# Blue_Clipper.net
KiCad netlist of a schematic drawn in Altium Designer
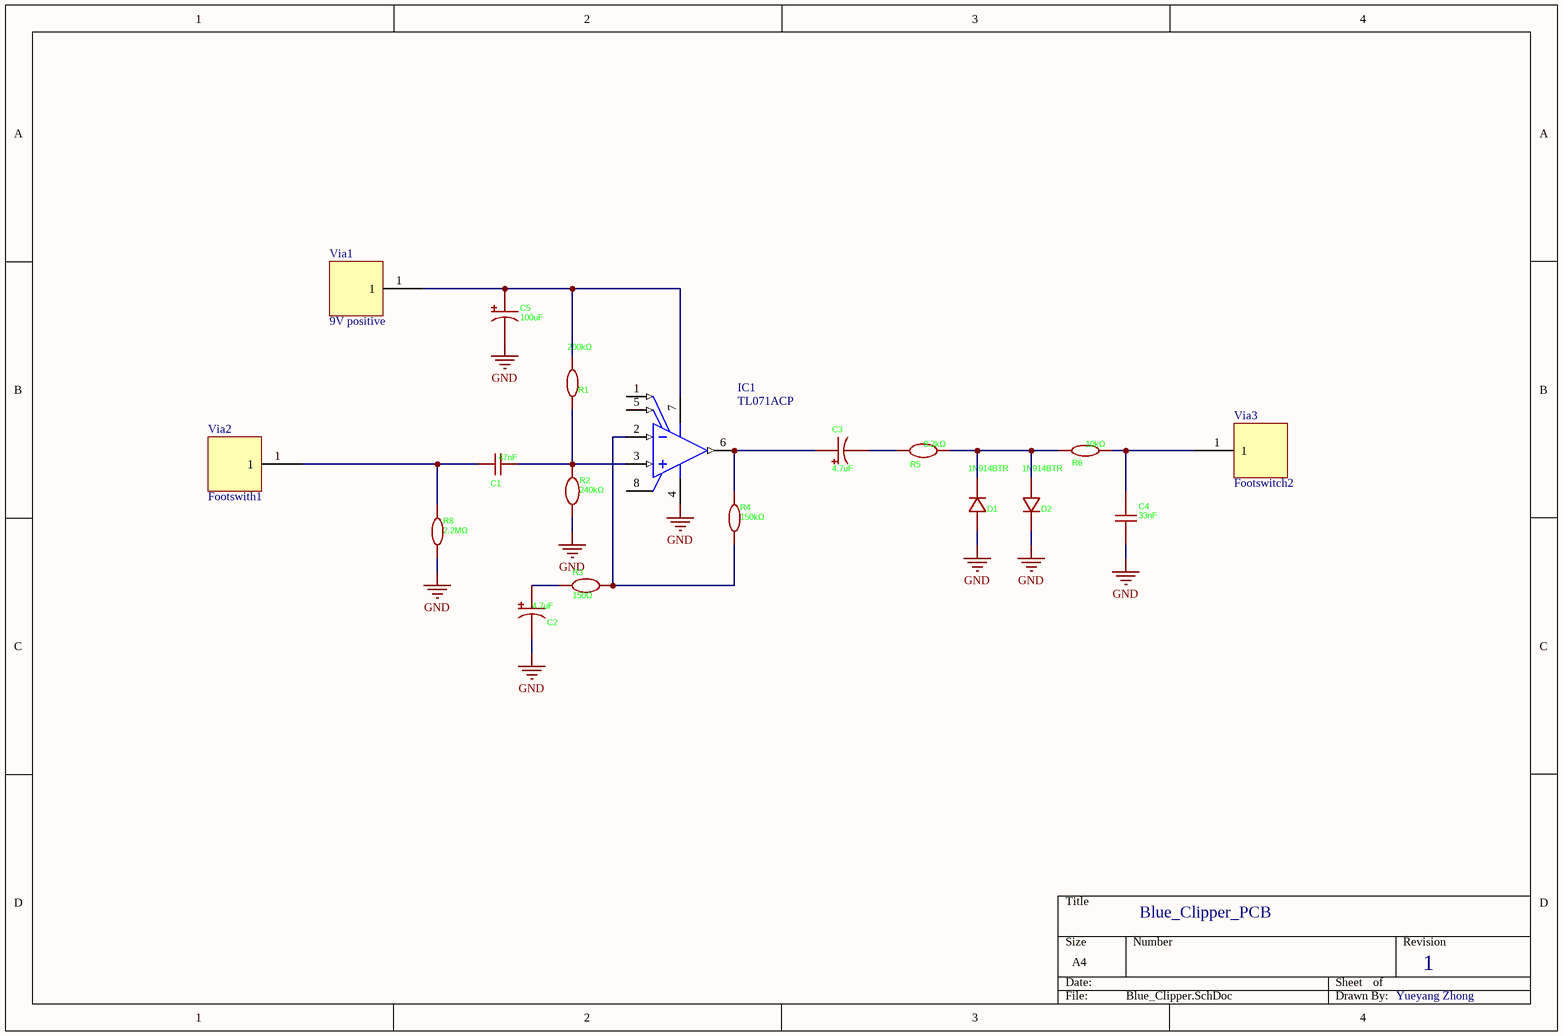
[diagram p0: Blue_Clipper.SchDoc]

(export (version "E")
  (design (tool "Eeschema 10.0.6"))
  (components
    (comp (ref "C1")
      (value "47nF")
      (footprint "47nF")
      (fields
        (field (name "MANUFACTURER") "SRD(圣融达)")
        (field (name "MANUFACTURER PART") "MPP473K2E1304095LC")
        (field (name "TOLERANCE") "±10%")
      )
      (libsource (lib "Schlib1") (part "MPP473K2E1304095LC"))
    )
    (comp (ref "C2")
      (value "4.7uF")
      (footprint "4.7uF")
      (fields
        (field (name "MANUFACTURER") "Nichicon(尼吉康)")
        (field (name "MANUFACTURER PART") "UUD1V4R7MCL1GS")
        (field (name "TOLERANCE") "±20%")
      )
      (libsource (lib "Schlib1") (part "UUD1V4R7MCL1GS"))
    )
    (comp (ref "C3")
      (value "4.7uF")
      (footprint "4.7uF")
      (fields
        (field (name "MANUFACTURER") "Nichicon(尼吉康)")
        (field (name "MANUFACTURER PART") "UUD1V4R7MCL1GS")
        (field (name "TOLERANCE") "±20%")
      )
      (libsource (lib "Schlib1") (part "UUD1V4R7MCL1GS"))
    )
    (comp (ref "C4")
      (value "33nF")
      (footprint "33nF")
      (fields
        (field (name "MANUFACTURER") "KYET(科雅)")
        (field (name "MANUFACTURER PART") "KP333J2J1001")
        (field (name "TOLERANCE") "±5%")
      )
      (libsource (lib "Schlib1") (part "KP333J2J1001"))
    )
    (comp (ref "C5")
      (value "100uF")
      (footprint "100nF")
      (fields
        (field (name "MANUFACTURER") "rubycon(红宝石)")
        (field (name "MANUFACTURER PART") "50TZV100M8X10.5")
        (field (name "TOLERANCE") "±20%")
      )
      (libsource (lib "Schlib1") (part "50TZV100M8X10.5"))
    )
    (comp (ref "D1")
      (value "1N914BTR")
      (footprint "DO-35_BD2.0-L4.2-P8.20-D0.5-RD")
      (fields (field (name "MANUFACTURER") "onsemi(安森美)"))
      (libsource (lib "diodes") (part "1N914BTR"))
    )
    (comp (ref "D2")
      (value "1N914BTR")
      (footprint "DO-35_BD2.0-L4.2-P8.20-D0.5-RD")
      (fields (field (name "MANUFACTURER") "onsemi(安森美)"))
      (libsource (lib "diodes") (part "1N914BTR"))
    )
    (comp (ref "IC1")
      (value "TL071ACP")
      (footprint "P0008A")
      (fields (field (name "MANUFACTURER") "Texas Instruments"))
      (libsource (lib "Altium Content Vault") (part "TI-AMP-S5-2-8"))
    )
    (comp (ref "R1")
      (value "200kΩ")
      (footprint "200K")
      (description "200K")
      (fields (field (name "MANUFACTURER") "VO(翔胜)") (field (name "MANUFACTURER PART") "CR1W-200K±5%-TT52"))
      (libsource (lib "Schlib1") (part "CR1W-200K±5%-TT52"))
    )
    (comp (ref "R2")
      (value "240kΩ")
      (footprint "240K")
      (description "240K")
      (fields (field (name "MANUFACTURER") "VO(翔胜)") (field (name "MANUFACTURER PART") "MO2W-240K±5%-9T73"))
      (libsource (lib "Schlib1") (part "MO2W-240K±5%-9T73"))
    )
    (comp (ref "R3")
      (value "150Ω")
      (footprint "150")
      (description "150")
      (fields (field (name "MANUFACTURER") "VO(翔胜)") (field (name "MANUFACTURER PART") "CR1/2W-150Ω±5%-XT52"))
      (libsource (lib "Schlib1") (part "CR1/2W-150Ω±5%-XT52"))
    )
    (comp (ref "R4")
      (value "150kΩ")
      (footprint "150K")
      (description "150K")
      (fields
        (field (name "MANUFACTURER") "UNI-ROYAL(厚声)")
        (field (name "MANUFACTURER PART") "MFR03SF1503A10")
      )
      (libsource (lib "Schlib1") (part "MFR03SF1503A10"))
    )
    (comp (ref "R5")
      (value "8.2kΩ")
      (footprint "8K2")
      (description "8.2K")
      (fields (field (name "MANUFACTURER") "VO(翔胜)") (field (name "MANUFACTURER PART") "CR1/2W-8K2±5%-2T52"))
      (libsource (lib "Schlib1") (part "CR1/2W-8K2±5%-2T52"))
    )
    (comp (ref "R6")
      (value "10kΩ")
      (footprint "10K")
      (description "10K")
      (fields (field (name "MANUFACTURER") "VO(翔胜)") (field (name "MANUFACTURER PART") "CR1/2W-10K±5%-2T52"))
      (libsource (lib "Schlib1") (part "CR1/2W-10K±5%-2T52"))
    )
    (comp (ref "R8")
      (value "2.2MΩ")
      (footprint "2.2M")
      (description "2.2M")
      (fields
        (field (name "MANUFACTURER") "CCO(千志电子)")
        (field (name "MANUFACTURER PART") "CF1/2W-2.2MΩ±5% T")
      )
      (libsource (lib "Schlib1") (part "CF1/2W-2.2MΩ±5% T"))
    )
    (comp (ref "Via1")
      (value "9V positive")
      (footprint "PCBComponent_1")
      (libsource (lib "Schlib1") (part "Via"))
    )
    (comp (ref "Via2")
      (value "Footswith1")
      (footprint "PCBComponent_1")
      (libsource (lib "Schlib1") (part "Via"))
    )
    (comp (ref "Via3") (value "Footswitch2") (footprint "PCBComponent_1") (libsource (lib "") (part "Via_1")))
  )
  (nets
    (net (code "1") (name "GND") (class "Default")
      (node (ref "C2") (pin "2") (pinfunction "2_2") (pintype "passive"))
      (node (ref "C4") (pin "1") (pinfunction "1_1") (pintype "passive"))
      (node (ref "C5") (pin "2") (pinfunction "2_2") (pintype "passive"))
      (node (ref "D1") (pin "2") (pinfunction "2_2") (pintype "passive"))
      (node (ref "D2") (pin "1") (pinfunction "1_1") (pintype "passive"))
      (node (ref "IC1") (pin "4") (pinfunction "VCC-_4") (pintype "power_in"))
      (node (ref "R2") (pin "1") (pinfunction "1_1") (pintype "passive"))
      (node (ref "R8") (pin "1") (pinfunction "1_1") (pintype "passive"))
    )
    (net (code "2") (name "Net-(C1-Pad1)") (class "Default")
      (node (ref "C1") (pin "1") (pinfunction "1_1") (pintype "passive"))
      (node (ref "R8") (pin "2") (pinfunction "2_2") (pintype "passive"))
      (node (ref "Via2") (pin "1") (pinfunction "1_1") (pintype "passive"))
    )
    (net (code "3") (name "Net-(C2-Pad1)") (class "Default")
      (node (ref "C2") (pin "1") (pinfunction "1_1") (pintype "passive"))
      (node (ref "R3") (pin "2") (pinfunction "2_2") (pintype "passive"))
    )
    (net (code "4") (name "Net-(C3-Pad2)") (class "Default")
      (node (ref "C3") (pin "2") (pinfunction "2_2") (pintype "passive"))
      (node (ref "R5") (pin "1") (pinfunction "1_1") (pintype "passive"))
    )
    (net (code "5") (name "Net-(C4-Pad2)") (class "Default")
      (node (ref "C4") (pin "2") (pinfunction "2_2") (pintype "passive"))
      (node (ref "R6") (pin "2") (pinfunction "2_2") (pintype "passive"))
      (node (ref "Via3") (pin "1") (pinfunction "1_1") (pintype "passive"))
    )
    (net (code "6") (name "Net-(D1-Pad1)") (class "Default")
      (node (ref "D1") (pin "1") (pinfunction "1_1") (pintype "passive"))
      (node (ref "D2") (pin "2") (pinfunction "2_2") (pintype "passive"))
      (node (ref "R5") (pin "2") (pinfunction "2_2") (pintype "passive"))
      (node (ref "R6") (pin "1") (pinfunction "1_1") (pintype "passive"))
    )
    (net (code "7") (name "Net-(IC1-IN+)") (class "Default")
      (node (ref "C1") (pin "2") (pinfunction "2_2") (pintype "passive"))
      (node (ref "IC1") (pin "3") (pinfunction "IN+_3") (pintype "input"))
      (node (ref "R1") (pin "1") (pinfunction "1_1") (pintype "passive"))
      (node (ref "R2") (pin "2") (pinfunction "2_2") (pintype "passive"))
    )
    (net (code "8") (name "Net-(IC1-IN-)") (class "Default")
      (node (ref "IC1") (pin "2") (pinfunction "IN-_2") (pintype "input"))
      (node (ref "R3") (pin "1") (pinfunction "1_1") (pintype "passive"))
      (node (ref "R4") (pin "2") (pinfunction "2_2") (pintype "passive"))
    )
    (net (code "9") (name "Net-(IC1-OUT)") (class "Default")
      (node (ref "C3") (pin "1") (pinfunction "1_1") (pintype "passive"))
      (node (ref "IC1") (pin "6") (pinfunction "OUT_6") (pintype "output"))
      (node (ref "R4") (pin "1") (pinfunction "1_1") (pintype "passive"))
    )
    (net (code "10") (name "Net-(IC1-VCC+)") (class "Default")
      (node (ref "C5") (pin "1") (pinfunction "1_1") (pintype "passive"))
      (node (ref "IC1") (pin "7") (pinfunction "VCC+_7") (pintype "power_in"))
      (node (ref "R1") (pin "2") (pinfunction "2_2") (pintype "passive"))
      (node (ref "Via1") (pin "1") (pinfunction "1_1") (pintype "passive"))
    )
    (net (code "11") (name "unconnected-(IC1-NC-Pad8)") (class "Default")
      (node (ref "IC1") (pin "8") (pinfunction "NC_8") (pintype "passive"))
    )
    (net (code "12") (name "unconnected-(IC1-OFFSET_N1-Pad1)") (class "Default")
      (node (ref "IC1") (pin "1") (pinfunction "OFFSET_N1_1") (pintype "input"))
    )
    (net (code "13") (name "unconnected-(IC1-OFFSET_N2-Pad5)") (class "Default")
      (node (ref "IC1") (pin "5") (pinfunction "OFFSET_N2_5") (pintype "input"))
    )
  )
)
